# first_prototype.net
KiCad netlist of a schematic drawn in EAGLE
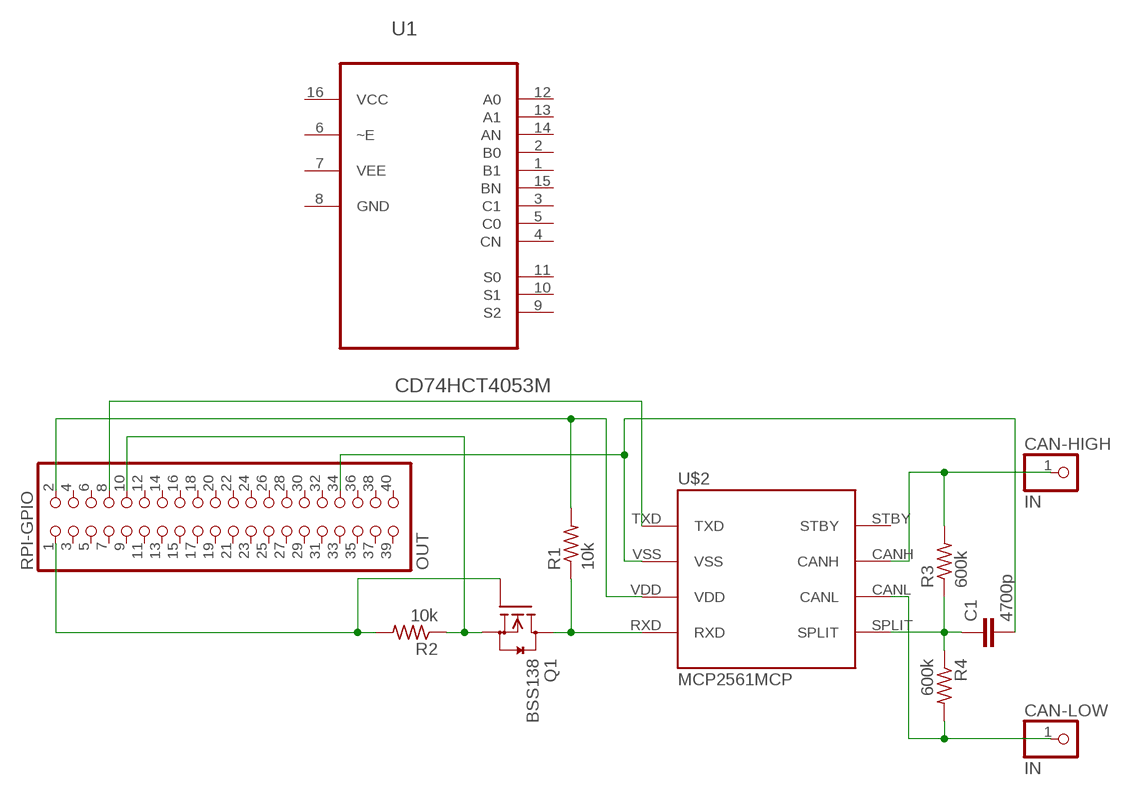
[diagram p0: schematic, sheet 1]

(export (version "E")
  (design (tool "Eeschema 10.0.6"))
  (components
    (comp (ref "C1")
      (value "4700p")
      (footprint "eagle-import:C2.5-2")
      (libsource (lib "eagle-import") (part "C2.5/2"))
    )
    (comp (ref "CAN-HIGH")
      (value "IN")
      (footprint "eagle-import:1X01")
      (libsource (lib "eagle-import") (part "PINHD-1X1"))
    )
    (comp (ref "CAN-LOW")
      (value "IN")
      (footprint "eagle-import:1X01")
      (libsource (lib "eagle-import") (part "PINHD-1X1"))
    )
    (comp (ref "Q1")
      (value "BSS138")
      (footprint "eagle-import:SOT23")
      (libsource (lib "eagle-import") (part "BSS138"))
    )
    (comp (ref "R1")
      (value "10k")
      (footprint "eagle-import:M2309")
      (libsource (lib "eagle-import") (part "R-US_M2309"))
    )
    (comp (ref "R2")
      (value "10k")
      (footprint "eagle-import:M2309")
      (libsource (lib "eagle-import") (part "R-US_M2309"))
    )
    (comp (ref "R3")
      (value "600k")
      (footprint "eagle-import:M2309")
      (libsource (lib "eagle-import") (part "R-US_M2309"))
    )
    (comp (ref "R4")
      (value "600k")
      (footprint "eagle-import:M2309")
      (libsource (lib "eagle-import") (part "R-US_M2309"))
    )
    (comp (ref "RPI-GPIO")
      (value "OUT")
      (footprint "eagle-import:2X20")
      (libsource (lib "eagle-import") (part "PINHD-2X20"))
    )
    (comp (ref "U$2")
      (value "MCP2561MCP")
      (footprint "eagle-import:MCP2561_PDIP")
      (libsource (lib "eagle-import") (part "MCP2561MCP"))
    )
    (comp (ref "U1")
      (value "CD74HCT4053M")
      (footprint "eagle-import:SOIC127P600X175-16N")
      (libsource (lib "eagle-import") (part "CD74HCT4053M"))
    )
  )
  (nets
    (net (code "1") (name "/VCC") (class "Default")
      (node (ref "U1") (pin "16") (pinfunction "VCC_16") (pintype "power_in"))
    )
    (net (code "2") (name "Net-(C1-Pad1)") (class "Default")
      (node (ref "C1") (pin "1") (pinfunction "1_1") (pintype "passive"))
      (node (ref "R3") (pin "1") (pinfunction "1_1") (pintype "passive"))
      (node (ref "R4") (pin "1") (pinfunction "1_1") (pintype "passive"))
      (node (ref "U$2") (pin "SPLIT") (pinfunction "SPLIT_SPLIT") (pintype "bidirectional"))
    )
    (net (code "3") (name "Net-(C1-Pad2)") (class "Default")
      (node (ref "C1") (pin "2") (pinfunction "2_2") (pintype "passive"))
      (node (ref "RPI-GPIO") (pin "34") (pinfunction "34_34") (pintype "passive"))
      (node (ref "U$2") (pin "VSS") (pinfunction "VSS_VSS") (pintype "bidirectional"))
    )
    (net (code "4") (name "Net-(CAN-HIGH-Pad1)") (class "Default")
      (node (ref "CAN-HIGH") (pin "1") (pinfunction "1_1") (pintype "passive"))
      (node (ref "R3") (pin "2") (pinfunction "2_2") (pintype "passive"))
      (node (ref "U$2") (pin "CANH") (pinfunction "CANH_CANH") (pintype "bidirectional"))
    )
    (net (code "5") (name "Net-(CAN-LOW-Pad1)") (class "Default")
      (node (ref "CAN-LOW") (pin "1") (pinfunction "1_1") (pintype "passive"))
      (node (ref "R4") (pin "2") (pinfunction "2_2") (pintype "passive"))
      (node (ref "U$2") (pin "CANL") (pinfunction "CANL_CANL") (pintype "bidirectional"))
    )
    (net (code "6") (name "Net-(Q1-D)") (class "Default")
      (node (ref "Q1") (pin "3") (pinfunction "D_3") (pintype "passive"))
      (node (ref "R1") (pin "1") (pinfunction "1_1") (pintype "passive"))
      (node (ref "U$2") (pin "RXD") (pinfunction "RXD_RXD") (pintype "bidirectional"))
    )
    (net (code "7") (name "Net-(Q1-G)") (class "Default")
      (node (ref "Q1") (pin "1") (pinfunction "G_1") (pintype "passive"))
      (node (ref "R2") (pin "2") (pinfunction "2_2") (pintype "passive"))
      (node (ref "RPI-GPIO") (pin "1") (pinfunction "1_1") (pintype "passive"))
    )
    (net (code "8") (name "Net-(Q1-S)") (class "Default")
      (node (ref "Q1") (pin "2") (pinfunction "S_2") (pintype "passive"))
      (node (ref "R2") (pin "1") (pinfunction "1_1") (pintype "passive"))
      (node (ref "RPI-GPIO") (pin "10") (pinfunction "10_10") (pintype "passive"))
    )
    (net (code "9") (name "Net-(R1-Pad2)") (class "Default")
      (node (ref "R1") (pin "2") (pinfunction "2_2") (pintype "passive"))
      (node (ref "RPI-GPIO") (pin "2") (pinfunction "2_2") (pintype "passive"))
      (node (ref "U$2") (pin "VDD") (pinfunction "VDD_VDD") (pintype "bidirectional"))
    )
    (net (code "10") (name "Net-(RPI-GPIO-Pad8)") (class "Default")
      (node (ref "RPI-GPIO") (pin "8") (pinfunction "8_8") (pintype "passive"))
      (node (ref "U$2") (pin "TXD") (pinfunction "TXD_TXD") (pintype "bidirectional"))
    )
    (net (code "11") (name "unconnected-(RPI-GPIO-Pad3)") (class "Default")
      (node (ref "RPI-GPIO") (pin "3") (pinfunction "3_3") (pintype "passive"))
    )
    (net (code "12") (name "unconnected-(RPI-GPIO-Pad4)") (class "Default")
      (node (ref "RPI-GPIO") (pin "4") (pinfunction "4_4") (pintype "passive"))
    )
    (net (code "13") (name "unconnected-(RPI-GPIO-Pad5)") (class "Default")
      (node (ref "RPI-GPIO") (pin "5") (pinfunction "5_5") (pintype "passive"))
    )
    (net (code "14") (name "unconnected-(RPI-GPIO-Pad6)") (class "Default")
      (node (ref "RPI-GPIO") (pin "6") (pinfunction "6_6") (pintype "passive"))
    )
    (net (code "15") (name "unconnected-(RPI-GPIO-Pad7)") (class "Default")
      (node (ref "RPI-GPIO") (pin "7") (pinfunction "7_7") (pintype "passive"))
    )
    (net (code "16") (name "unconnected-(RPI-GPIO-Pad9)") (class "Default")
      (node (ref "RPI-GPIO") (pin "9") (pinfunction "9_9") (pintype "passive"))
    )
    (net (code "17") (name "unconnected-(RPI-GPIO-Pad11)") (class "Default")
      (node (ref "RPI-GPIO") (pin "11") (pinfunction "11_11") (pintype "passive"))
    )
    (net (code "18") (name "unconnected-(RPI-GPIO-Pad12)") (class "Default")
      (node (ref "RPI-GPIO") (pin "12") (pinfunction "12_12") (pintype "passive"))
    )
    (net (code "19") (name "unconnected-(RPI-GPIO-Pad13)") (class "Default")
      (node (ref "RPI-GPIO") (pin "13") (pinfunction "13_13") (pintype "passive"))
    )
    (net (code "20") (name "unconnected-(RPI-GPIO-Pad14)") (class "Default")
      (node (ref "RPI-GPIO") (pin "14") (pinfunction "14_14") (pintype "passive"))
    )
    (net (code "21") (name "unconnected-(RPI-GPIO-Pad15)") (class "Default")
      (node (ref "RPI-GPIO") (pin "15") (pinfunction "15_15") (pintype "passive"))
    )
    (net (code "22") (name "unconnected-(RPI-GPIO-Pad16)") (class "Default")
      (node (ref "RPI-GPIO") (pin "16") (pinfunction "16_16") (pintype "passive"))
    )
    (net (code "23") (name "unconnected-(RPI-GPIO-Pad17)") (class "Default")
      (node (ref "RPI-GPIO") (pin "17") (pinfunction "17_17") (pintype "passive"))
    )
    (net (code "24") (name "unconnected-(RPI-GPIO-Pad18)") (class "Default")
      (node (ref "RPI-GPIO") (pin "18") (pinfunction "18_18") (pintype "passive"))
    )
    (net (code "25") (name "unconnected-(RPI-GPIO-Pad19)") (class "Default")
      (node (ref "RPI-GPIO") (pin "19") (pinfunction "19_19") (pintype "passive"))
    )
    (net (code "26") (name "unconnected-(RPI-GPIO-Pad20)") (class "Default")
      (node (ref "RPI-GPIO") (pin "20") (pinfunction "20_20") (pintype "passive"))
    )
    (net (code "27") (name "unconnected-(RPI-GPIO-Pad21)") (class "Default")
      (node (ref "RPI-GPIO") (pin "21") (pinfunction "21_21") (pintype "passive"))
    )
    (net (code "28") (name "unconnected-(RPI-GPIO-Pad22)") (class "Default")
      (node (ref "RPI-GPIO") (pin "22") (pinfunction "22_22") (pintype "passive"))
    )
    (net (code "29") (name "unconnected-(RPI-GPIO-Pad23)") (class "Default")
      (node (ref "RPI-GPIO") (pin "23") (pinfunction "23_23") (pintype "passive"))
    )
    (net (code "30") (name "unconnected-(RPI-GPIO-Pad24)") (class "Default")
      (node (ref "RPI-GPIO") (pin "24") (pinfunction "24_24") (pintype "passive"))
    )
    (net (code "31") (name "unconnected-(RPI-GPIO-Pad25)") (class "Default")
      (node (ref "RPI-GPIO") (pin "25") (pinfunction "25_25") (pintype "passive"))
    )
    (net (code "32") (name "unconnected-(RPI-GPIO-Pad26)") (class "Default")
      (node (ref "RPI-GPIO") (pin "26") (pinfunction "26_26") (pintype "passive"))
    )
    (net (code "33") (name "unconnected-(RPI-GPIO-Pad27)") (class "Default")
      (node (ref "RPI-GPIO") (pin "27") (pinfunction "27_27") (pintype "passive"))
    )
    (net (code "34") (name "unconnected-(RPI-GPIO-Pad28)") (class "Default")
      (node (ref "RPI-GPIO") (pin "28") (pinfunction "28_28") (pintype "passive"))
    )
    (net (code "35") (name "unconnected-(RPI-GPIO-Pad29)") (class "Default")
      (node (ref "RPI-GPIO") (pin "29") (pinfunction "29_29") (pintype "passive"))
    )
    (net (code "36") (name "unconnected-(RPI-GPIO-Pad30)") (class "Default")
      (node (ref "RPI-GPIO") (pin "30") (pinfunction "30_30") (pintype "passive"))
    )
    (net (code "37") (name "unconnected-(RPI-GPIO-Pad31)") (class "Default")
      (node (ref "RPI-GPIO") (pin "31") (pinfunction "31_31") (pintype "passive"))
    )
    (net (code "38") (name "unconnected-(RPI-GPIO-Pad32)") (class "Default")
      (node (ref "RPI-GPIO") (pin "32") (pinfunction "32_32") (pintype "passive"))
    )
    (net (code "39") (name "unconnected-(RPI-GPIO-Pad33)") (class "Default")
      (node (ref "RPI-GPIO") (pin "33") (pinfunction "33_33") (pintype "passive"))
    )
    (net (code "40") (name "unconnected-(RPI-GPIO-Pad35)") (class "Default")
      (node (ref "RPI-GPIO") (pin "35") (pinfunction "35_35") (pintype "passive"))
    )
    (net (code "41") (name "unconnected-(RPI-GPIO-Pad36)") (class "Default")
      (node (ref "RPI-GPIO") (pin "36") (pinfunction "36_36") (pintype "passive"))
    )
    (net (code "42") (name "unconnected-(RPI-GPIO-Pad37)") (class "Default")
      (node (ref "RPI-GPIO") (pin "37") (pinfunction "37_37") (pintype "passive"))
    )
    (net (code "43") (name "unconnected-(RPI-GPIO-Pad38)") (class "Default")
      (node (ref "RPI-GPIO") (pin "38") (pinfunction "38_38") (pintype "passive"))
    )
    (net (code "44") (name "unconnected-(RPI-GPIO-Pad39)") (class "Default")
      (node (ref "RPI-GPIO") (pin "39") (pinfunction "39_39") (pintype "passive"))
    )
    (net (code "45") (name "unconnected-(RPI-GPIO-Pad40)") (class "Default")
      (node (ref "RPI-GPIO") (pin "40") (pinfunction "40_40") (pintype "passive"))
    )
    (net (code "46") (name "unconnected-(U$2-PadSTBY)") (class "Default")
      (node (ref "U$2") (pin "STBY") (pinfunction "STBY_STBY") (pintype "bidirectional"))
    )
    (net (code "47") (name "unconnected-(U1-A0-Pad12)") (class "Default")
      (node (ref "U1") (pin "12") (pinfunction "A0_12") (pintype "bidirectional"))
    )
    (net (code "48") (name "unconnected-(U1-A1-Pad13)") (class "Default")
      (node (ref "U1") (pin "13") (pinfunction "A1_13") (pintype "bidirectional"))
    )
    (net (code "49") (name "unconnected-(U1-AN-Pad14)") (class "Default")
      (node (ref "U1") (pin "14") (pinfunction "AN_14") (pintype "bidirectional"))
    )
    (net (code "50") (name "unconnected-(U1-B0-Pad2)") (class "Default")
      (node (ref "U1") (pin "2") (pinfunction "B0_2") (pintype "bidirectional"))
    )
    (net (code "51") (name "unconnected-(U1-B1-Pad1)") (class "Default")
      (node (ref "U1") (pin "1") (pinfunction "B1_1") (pintype "bidirectional"))
    )
    (net (code "52") (name "unconnected-(U1-BN-Pad15)") (class "Default")
      (node (ref "U1") (pin "15") (pinfunction "BN_15") (pintype "bidirectional"))
    )
    (net (code "53") (name "unconnected-(U1-C0-Pad5)") (class "Default")
      (node (ref "U1") (pin "5") (pinfunction "C0_5") (pintype "bidirectional"))
    )
    (net (code "54") (name "unconnected-(U1-C1-Pad3)") (class "Default")
      (node (ref "U1") (pin "3") (pinfunction "C1_3") (pintype "bidirectional"))
    )
    (net (code "55") (name "unconnected-(U1-CN-Pad4)") (class "Default")
      (node (ref "U1") (pin "4") (pinfunction "CN_4") (pintype "bidirectional"))
    )
    (net (code "56") (name "unconnected-(U1-GND-Pad8)") (class "Default")
      (node (ref "U1") (pin "8") (pinfunction "GND_8") (pintype "passive"))
    )
    (net (code "57") (name "unconnected-(U1-S0-Pad11)") (class "Default")
      (node (ref "U1") (pin "11") (pinfunction "S0_11") (pintype "bidirectional"))
    )
    (net (code "58") (name "unconnected-(U1-S1-Pad10)") (class "Default")
      (node (ref "U1") (pin "10") (pinfunction "S1_10") (pintype "bidirectional"))
    )
    (net (code "59") (name "unconnected-(U1-S2-Pad9)") (class "Default")
      (node (ref "U1") (pin "9") (pinfunction "S2_9") (pintype "bidirectional"))
    )
    (net (code "60") (name "unconnected-(U1-VEE-Pad7)") (class "Default")
      (node (ref "U1") (pin "7") (pinfunction "VEE_7") (pintype "input"))
    )
    (net (code "61") (name "unconnected-(U1-~{E}-Pad6)") (class "Default")
      (node (ref "U1") (pin "6") (pinfunction "~{E}_6") (pintype "input"))
    )
  )
)
